# modbrainsv0_4.net
KiCad netlist of a schematic drawn in EAGLE
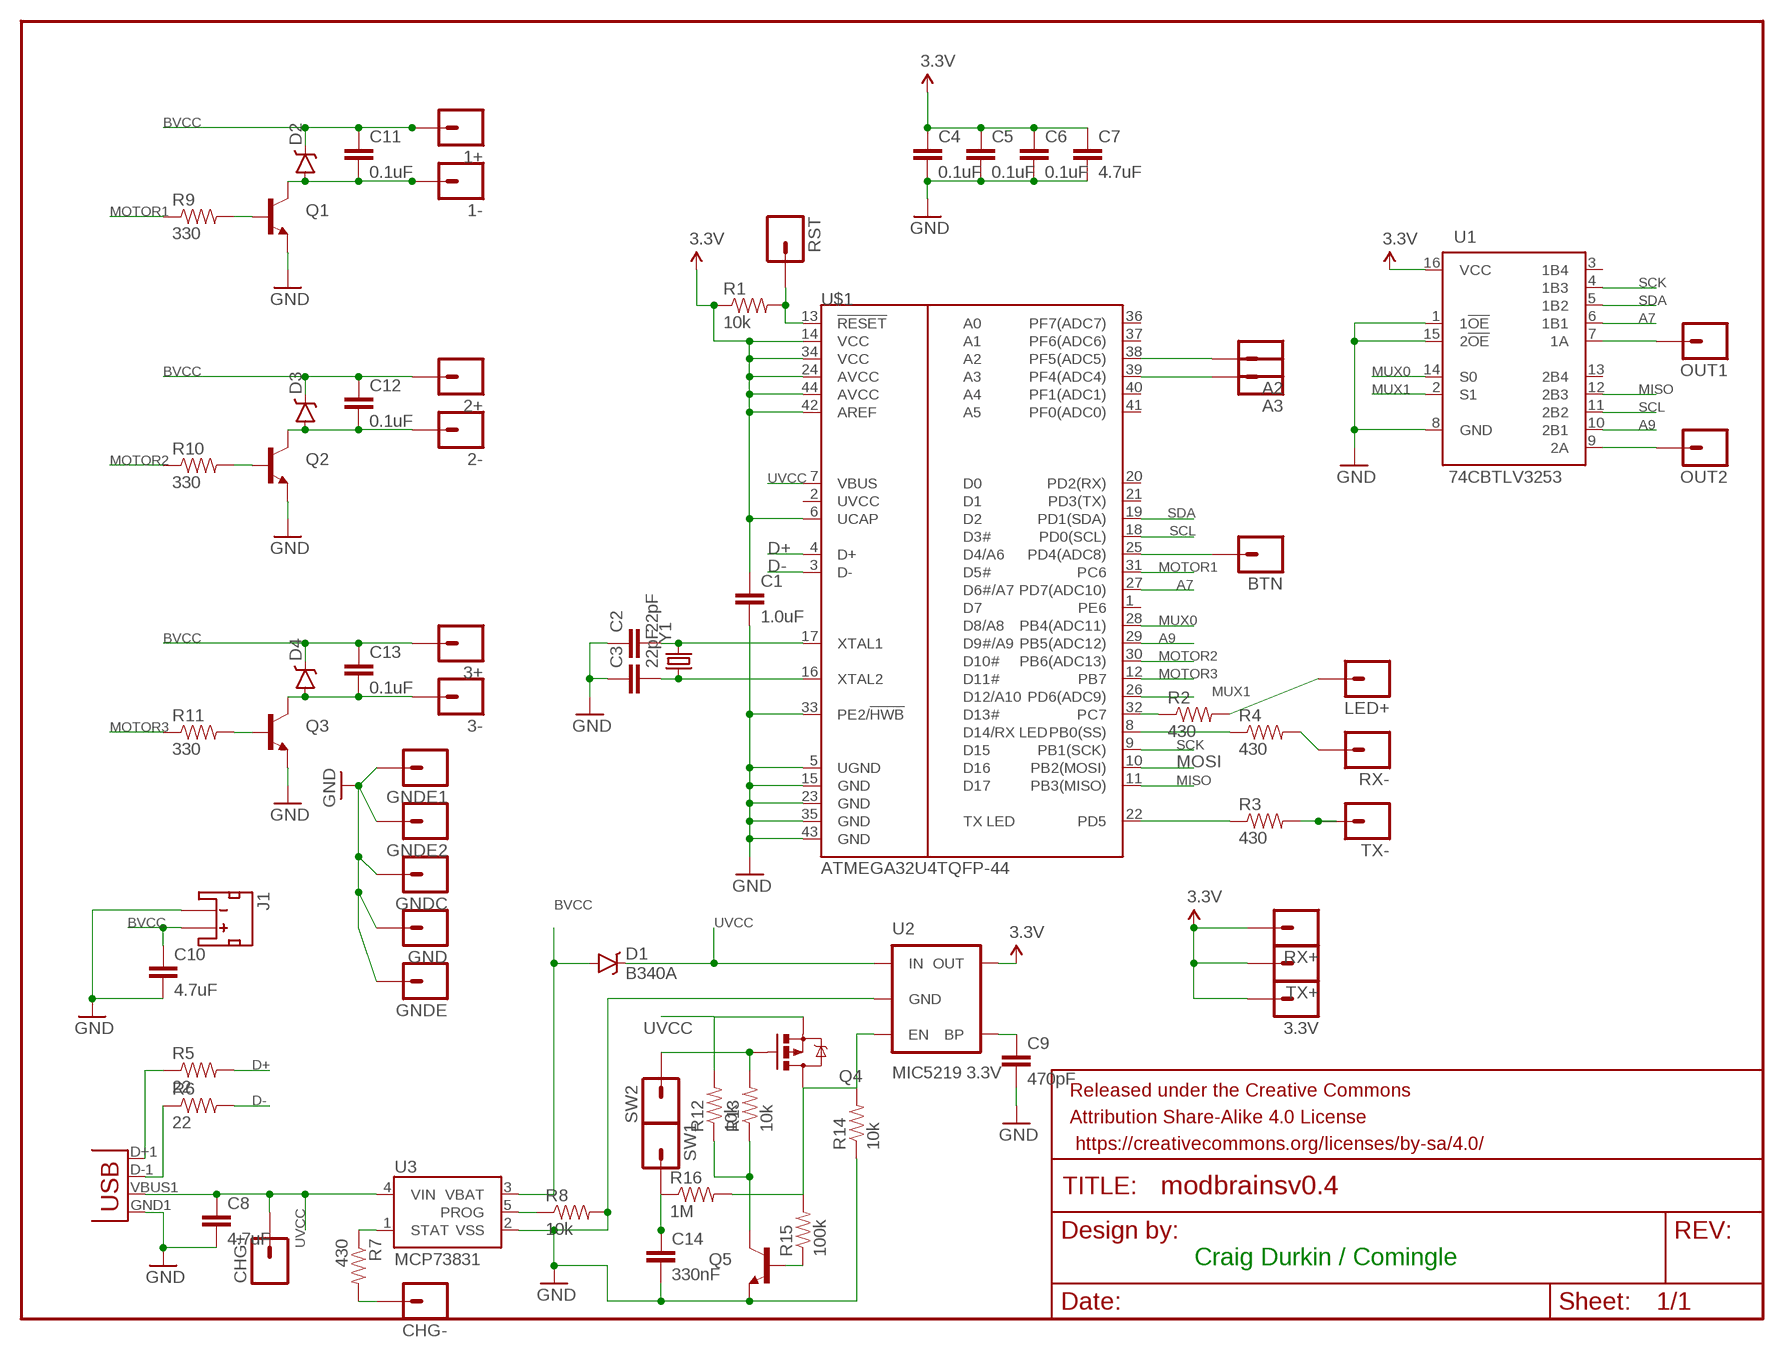
[diagram p0: schematic, sheet 1]

(export (version "E")
  (design (tool "Eeschema 10.0.6"))
  (components
    (comp (ref "1+")
      (value "M01PTH")
      (footprint "eagle-import:1X01")
      (libsource (lib "eagle-import") (part "M01PTH"))
    )
    (comp (ref "1-")
      (value "M01PTH")
      (footprint "eagle-import:1X01")
      (libsource (lib "eagle-import") (part "M01PTH"))
    )
    (comp (ref "2+")
      (value "M01PTH")
      (footprint "eagle-import:1X01")
      (libsource (lib "eagle-import") (part "M01PTH"))
    )
    (comp (ref "2-")
      (value "M01PTH")
      (footprint "eagle-import:1X01")
      (libsource (lib "eagle-import") (part "M01PTH"))
    )
    (comp (ref "3+")
      (value "M01PTH")
      (footprint "eagle-import:1X01")
      (libsource (lib "eagle-import") (part "M01PTH"))
    )
    (comp (ref "3-")
      (value "M01PTH")
      (footprint "eagle-import:1X01")
      (libsource (lib "eagle-import") (part "M01PTH"))
    )
    (comp (ref "3.3V")
      (value "M01PTH")
      (footprint "eagle-import:1X01")
      (libsource (lib "eagle-import") (part "M01PTH"))
    )
    (comp (ref "A2")
      (value "M01PTH")
      (footprint "eagle-import:1X01")
      (libsource (lib "eagle-import") (part "M01PTH"))
    )
    (comp (ref "A3")
      (value "M01PTH")
      (footprint "eagle-import:1X01")
      (libsource (lib "eagle-import") (part "M01PTH"))
    )
    (comp (ref "BTN")
      (value "M01PTH")
      (footprint "eagle-import:1X01")
      (libsource (lib "eagle-import") (part "M01PTH"))
    )
    (comp (ref "C1")
      (value "1.0uF")
      (footprint "eagle-import:0603-CAP")
      (libsource (lib "eagle-import") (part "1.0UF-16V-10%(0603)"))
    )
    (comp (ref "C2")
      (value "22pF")
      (footprint "eagle-import:0603-CAP")
      (libsource (lib "eagle-import") (part "22PF-50V-5%(0603)"))
    )
    (comp (ref "C3")
      (value "22pF")
      (footprint "eagle-import:0603-CAP")
      (libsource (lib "eagle-import") (part "22PF-50V-5%(0603)"))
    )
    (comp (ref "C4")
      (value "0.1uF")
      (footprint "eagle-import:0603-CAP")
      (libsource (lib "eagle-import") (part "SparkFun-Passives_CAP0603-CAP"))
    )
    (comp (ref "C5")
      (value "0.1uF")
      (footprint "eagle-import:0603-CAP")
      (libsource (lib "eagle-import") (part "SparkFun-Passives_CAP0603-CAP"))
    )
    (comp (ref "C6")
      (value "0.1uF")
      (footprint "eagle-import:0603-CAP")
      (libsource (lib "eagle-import") (part "SparkFun-Passives_CAP0603-CAP"))
    )
    (comp (ref "C7")
      (value "4.7uF")
      (footprint "eagle-import:0603-CAP")
      (libsource (lib "eagle-import") (part "SparkFun-Passives_CAP0603-CAP"))
    )
    (comp (ref "C8")
      (value "4.7uF")
      (footprint "eagle-import:1206")
      (libsource (lib "eagle-import") (part "SparkFun-Passives_CAP1206"))
    )
    (comp (ref "C9")
      (value "470pF")
      (footprint "eagle-import:0603-CAP")
      (libsource (lib "eagle-import") (part "0.1UF-25V(+80/-20%)(0603)"))
    )
    (comp (ref "C10")
      (value "4.7uF")
      (footprint "eagle-import:1206")
      (libsource (lib "eagle-import") (part "SparkFun-Passives_CAP1206"))
    )
    (comp (ref "C11")
      (value "0.1uF")
      (footprint "eagle-import:0603-CAP")
      (libsource (lib "eagle-import") (part "0.1UF-25V(+80/-20%)(0603)"))
    )
    (comp (ref "C12")
      (value "0.1uF")
      (footprint "eagle-import:0603-CAP")
      (libsource (lib "eagle-import") (part "0.1UF-25V(+80/-20%)(0603)"))
    )
    (comp (ref "C13")
      (value "0.1uF")
      (footprint "eagle-import:0603-CAP")
      (libsource (lib "eagle-import") (part "0.1UF-25V(+80/-20%)(0603)"))
    )
    (comp (ref "C14")
      (value "330nF")
      (footprint "eagle-import:0603-CAP")
      (libsource (lib "eagle-import") (part "CAP0603-CAP"))
    )
    (comp (ref "CHG+")
      (value "M01PTH")
      (footprint "eagle-import:1X01")
      (libsource (lib "eagle-import") (part "M01PTH"))
    )
    (comp (ref "CHG-")
      (value "M01PTH")
      (footprint "eagle-import:1X01")
      (libsource (lib "eagle-import") (part "M01PTH"))
    )
    (comp (ref "D1")
      (value "B340A")
      (footprint "eagle-import:SMA-DIODE")
      (libsource (lib "eagle-import") (part "DIODE-SCHOTTKY-B340A"))
    )
    (comp (ref "D2")
      (value "BAT20JFILM")
      (footprint "eagle-import:SOD-323")
      (libsource (lib "eagle-import") (part "BAT20JFILM"))
    )
    (comp (ref "D3")
      (value "BAT20JFILM")
      (footprint "eagle-import:SOD-323")
      (libsource (lib "eagle-import") (part "BAT20JFILM"))
    )
    (comp (ref "D4")
      (value "BAT20JFILM")
      (footprint "eagle-import:SOD-323")
      (libsource (lib "eagle-import") (part "BAT20JFILM"))
    )
    (comp (ref "FRAME1")
      (value "FRAME-LETTER")
      (footprint "eagle-import:CREATIVE_COMMONS")
      (libsource (lib "eagle-import") (part "FRAME-LETTER"))
    )
    (comp (ref "GND")
      (value "M01PTH")
      (footprint "eagle-import:1X01")
      (libsource (lib "eagle-import") (part "M01PTH"))
    )
    (comp (ref "GNDC")
      (value "M01PTH")
      (footprint "eagle-import:1X01")
      (libsource (lib "eagle-import") (part "M01PTH"))
    )
    (comp (ref "GNDE")
      (value "M01PTH")
      (footprint "eagle-import:1X01")
      (libsource (lib "eagle-import") (part "M01PTH"))
    )
    (comp (ref "GNDE1")
      (value "M01PTH")
      (footprint "eagle-import:1X01")
      (libsource (lib "eagle-import") (part "M01PTH"))
    )
    (comp (ref "GNDE2")
      (value "M01PTH")
      (footprint "eagle-import:1X01")
      (libsource (lib "eagle-import") (part "M01PTH"))
    )
    (comp (ref "J1")
      (value "JST_2MM_MALE")
      (footprint "eagle-import:JST-2-SMD")
      (libsource (lib "eagle-import") (part "JST_2MM_MALE"))
    )
    (comp (ref "JP4")
      (value "USB")
      (footprint "eagle-import:USB-B-MICRO-SMD_V03")
      (libsource (lib "eagle-import") (part "USB"))
    )
    (comp (ref "LED+")
      (value "M01PTH")
      (footprint "eagle-import:1X01")
      (libsource (lib "eagle-import") (part "M01PTH"))
    )
    (comp (ref "OUT1")
      (value "M01PTH")
      (footprint "eagle-import:1X01")
      (libsource (lib "eagle-import") (part "M01PTH"))
    )
    (comp (ref "OUT2")
      (value "M01PTH")
      (footprint "eagle-import:1X01")
      (libsource (lib "eagle-import") (part "M01PTH"))
    )
    (comp (ref "Q1")
      (value "TRANSISTOR_NPNSOT23-3")
      (footprint "eagle-import:SOT23-3")
      (libsource (lib "eagle-import") (part "TRANSISTOR_NPNSOT23-3"))
    )
    (comp (ref "Q2")
      (value "TRANSISTOR_NPNSOT23-3")
      (footprint "eagle-import:SOT23-3")
      (libsource (lib "eagle-import") (part "TRANSISTOR_NPNSOT23-3"))
    )
    (comp (ref "Q3")
      (value "TRANSISTOR_NPNSOT23-3")
      (footprint "eagle-import:SOT23-3")
      (libsource (lib "eagle-import") (part "TRANSISTOR_NPNSOT23-3"))
    )
    (comp (ref "Q4")
      (value "MOSFET-PCHANNEL")
      (footprint "eagle-import:SOT23-3")
      (libsource (lib "eagle-import") (part "MOSFET-PCHANNEL"))
    )
    (comp (ref "Q5")
      (value "MMBT2222A")
      (footprint "eagle-import:SOT23-3")
      (libsource (lib "eagle-import") (part "TRANSISTOR_NPNMMBT2222A"))
    )
    (comp (ref "R1")
      (value "10k")
      (footprint "eagle-import:0603-RES")
      (libsource (lib "eagle-import") (part "RESISTOR0603-RES"))
    )
    (comp (ref "R2")
      (value "430")
      (footprint "eagle-import:0603-RES")
      (libsource (lib "eagle-import") (part "RESISTOR0603"))
    )
    (comp (ref "R3")
      (value "430")
      (footprint "eagle-import:0603-RES")
      (libsource (lib "eagle-import") (part "RESISTOR0603"))
    )
    (comp (ref "R4")
      (value "430")
      (footprint "eagle-import:0603-RES")
      (libsource (lib "eagle-import") (part "RESISTOR0603"))
    )
    (comp (ref "R5")
      (value "22")
      (footprint "eagle-import:0603-RES")
      (libsource (lib "eagle-import") (part "RESISTOR0603-RES"))
    )
    (comp (ref "R6")
      (value "22")
      (footprint "eagle-import:0603-RES")
      (libsource (lib "eagle-import") (part "RESISTOR0603-RES"))
    )
    (comp (ref "R7")
      (value "430")
      (footprint "eagle-import:0603-RES")
      (libsource (lib "eagle-import") (part "RESISTOR0603-RES"))
    )
    (comp (ref "R8")
      (value "10k")
      (footprint "eagle-import:0603-RES")
      (libsource (lib "eagle-import") (part "RESISTOR0603-RES"))
    )
    (comp (ref "R9")
      (value "330")
      (footprint "eagle-import:0603-RES")
      (libsource (lib "eagle-import") (part "RESISTOR0603-RES"))
    )
    (comp (ref "R10")
      (value "330")
      (footprint "eagle-import:0603-RES")
      (libsource (lib "eagle-import") (part "RESISTOR0603-RES"))
    )
    (comp (ref "R11")
      (value "330")
      (footprint "eagle-import:0603-RES")
      (libsource (lib "eagle-import") (part "RESISTOR0603-RES"))
    )
    (comp (ref "R12")
      (value "10k")
      (footprint "eagle-import:0603-RES")
      (libsource (lib "eagle-import") (part "RESISTOR0603-RES"))
    )
    (comp (ref "R13")
      (value "10k")
      (footprint "eagle-import:0603-RES")
      (libsource (lib "eagle-import") (part "RESISTOR0603-RES"))
    )
    (comp (ref "R14")
      (value "10k")
      (footprint "eagle-import:0603-RES")
      (libsource (lib "eagle-import") (part "RESISTOR0603-RES"))
    )
    (comp (ref "R15")
      (value "100k")
      (footprint "eagle-import:0603-RES")
      (libsource (lib "eagle-import") (part "RESISTOR0603-RES"))
    )
    (comp (ref "R16")
      (value "1M")
      (footprint "eagle-import:0603-RES")
      (libsource (lib "eagle-import") (part "RESISTOR0603-RES"))
    )
    (comp (ref "RST")
      (value "M01PTH")
      (footprint "eagle-import:1X01")
      (libsource (lib "eagle-import") (part "M01PTH"))
    )
    (comp (ref "RX+")
      (value "M01PTH")
      (footprint "eagle-import:1X01")
      (libsource (lib "eagle-import") (part "M01PTH"))
    )
    (comp (ref "RX-")
      (value "M01PTH")
      (footprint "eagle-import:1X01")
      (libsource (lib "eagle-import") (part "M01PTH"))
    )
    (comp (ref "SW1")
      (value "M01PTH")
      (footprint "eagle-import:1X01")
      (libsource (lib "eagle-import") (part "M01PTH"))
    )
    (comp (ref "SW2")
      (value "M01PTH")
      (footprint "eagle-import:1X01")
      (libsource (lib "eagle-import") (part "M01PTH"))
    )
    (comp (ref "TX+")
      (value "M01PTH")
      (footprint "eagle-import:1X01")
      (libsource (lib "eagle-import") (part "M01PTH"))
    )
    (comp (ref "TX-")
      (value "M01PTH")
      (footprint "eagle-import:1X01")
      (libsource (lib "eagle-import") (part "M01PTH"))
    )
    (comp (ref "U$1")
      (value "ATMEGA32U4TQFP-44")
      (footprint "eagle-import:TQFP44")
      (libsource (lib "eagle-import") (part "ATMEGA32U4TQFP-44"))
    )
    (comp (ref "U1")
      (value "74CBTLV3253")
      (footprint "eagle-import:SSOP16-PRACTICE")
      (libsource (lib "eagle-import") (part "74CBTLV3253"))
    )
    (comp (ref "U2")
      (value "MIC5219 3.3V")
      (footprint "eagle-import:SOT23-5")
      (libsource (lib "eagle-import") (part "V_REG_MIC52193.3V"))
    )
    (comp (ref "U3")
      (value "MCP73831")
      (footprint "eagle-import:SOT23-5")
      (libsource (lib "eagle-import") (part "MCP73831"))
    )
    (comp (ref "Y1")
      (value "CRYSTAL5X3")
      (footprint "eagle-import:CRYSTAL-SMD-5X3")
      (libsource (lib "eagle-import") (part "CRYSTAL5X3"))
    )
  )
  (nets
    (net (code "1") (name "/A7") (class "Default")
      (node (ref "U$1") (pin "27") (pinfunction "PD7(ADC10)_27") (pintype "bidirectional"))
      (node (ref "U1") (pin "6") (pinfunction "1B1_6") (pintype "bidirectional"))
    )
    (net (code "2") (name "/A9") (class "Default")
      (node (ref "U$1") (pin "29") (pinfunction "PB5(ADC12)_29") (pintype "bidirectional"))
      (node (ref "U1") (pin "10") (pinfunction "2B1_10") (pintype "bidirectional"))
    )
    (net (code "3") (name "/BVCC") (class "Default")
      (node (ref "1+") (pin "1") (pinfunction "1_1") (pintype "passive"))
      (node (ref "2+") (pin "1") (pinfunction "1_1") (pintype "passive"))
      (node (ref "3+") (pin "1") (pinfunction "1_1") (pintype "passive"))
      (node (ref "C10") (pin "1") (pinfunction "1_1") (pintype "passive"))
      (node (ref "C11") (pin "1") (pinfunction "1_1") (pintype "passive"))
      (node (ref "C12") (pin "1") (pinfunction "1_1") (pintype "passive"))
      (node (ref "C13") (pin "1") (pinfunction "1_1") (pintype "passive"))
      (node (ref "D1") (pin "A") (pinfunction "A_A") (pintype "passive"))
      (node (ref "D2") (pin "C") (pinfunction "C_C") (pintype "passive"))
      (node (ref "D3") (pin "C") (pinfunction "C_C") (pintype "passive"))
      (node (ref "D4") (pin "C") (pinfunction "C_C") (pintype "passive"))
      (node (ref "J1") (pin "2") (pinfunction "+_2") (pintype "bidirectional"))
      (node (ref "U3") (pin "3") (pinfunction "VBAT_3") (pintype "power_in"))
    )
    (net (code "4") (name "/D+") (class "Default")
      (node (ref "R5") (pin "2") (pinfunction "2_2") (pintype "passive"))
      (node (ref "U$1") (pin "4") (pinfunction "D+_4") (pintype "bidirectional"))
    )
    (net (code "5") (name "/D-") (class "Default")
      (node (ref "R6") (pin "2") (pinfunction "2_2") (pintype "passive"))
      (node (ref "U$1") (pin "3") (pinfunction "D-_3") (pintype "bidirectional"))
    )
    (net (code "6") (name "/MISO") (class "Default")
      (node (ref "U$1") (pin "11") (pinfunction "PB3(MISO)_11") (pintype "bidirectional"))
      (node (ref "U1") (pin "12") (pinfunction "2B3_12") (pintype "bidirectional"))
    )
    (net (code "7") (name "/MOSI") (class "Default")
      (node (ref "U$1") (pin "10") (pinfunction "PB2(MOSI)_10") (pintype "bidirectional"))
    )
    (net (code "8") (name "/MOTOR1") (class "Default")
      (node (ref "R9") (pin "1") (pinfunction "1_1") (pintype "passive"))
      (node (ref "U$1") (pin "31") (pinfunction "PC6_31") (pintype "bidirectional"))
    )
    (net (code "9") (name "/MOTOR2") (class "Default")
      (node (ref "R10") (pin "1") (pinfunction "1_1") (pintype "passive"))
      (node (ref "U$1") (pin "30") (pinfunction "PB6(ADC13)_30") (pintype "bidirectional"))
    )
    (net (code "10") (name "/MOTOR3") (class "Default")
      (node (ref "R11") (pin "1") (pinfunction "1_1") (pintype "passive"))
      (node (ref "U$1") (pin "12") (pinfunction "PB7_12") (pintype "bidirectional"))
    )
    (net (code "11") (name "/MUX0") (class "Default")
      (node (ref "U$1") (pin "28") (pinfunction "PB4(ADC11)_28") (pintype "bidirectional"))
      (node (ref "U1") (pin "14") (pinfunction "S0_14") (pintype "bidirectional"))
    )
    (net (code "12") (name "/MUX1") (class "Default")
      (node (ref "U$1") (pin "26") (pinfunction "PD6(ADC9)_26") (pintype "bidirectional"))
      (node (ref "U1") (pin "2") (pinfunction "S1_2") (pintype "bidirectional"))
    )
    (net (code "13") (name "/SCK") (class "Default")
      (node (ref "U$1") (pin "9") (pinfunction "PB1(SCK)_9") (pintype "bidirectional"))
      (node (ref "U1") (pin "4") (pinfunction "1B3_4") (pintype "bidirectional"))
    )
    (net (code "14") (name "/SCL") (class "Default")
      (node (ref "U$1") (pin "18") (pinfunction "PD0(SCL)_18") (pintype "bidirectional"))
      (node (ref "U1") (pin "11") (pinfunction "2B2_11") (pintype "bidirectional"))
    )
    (net (code "15") (name "/SDA") (class "Default")
      (node (ref "U$1") (pin "19") (pinfunction "PD1(SDA)_19") (pintype "bidirectional"))
      (node (ref "U1") (pin "5") (pinfunction "1B2_5") (pintype "bidirectional"))
    )
    (net (code "16") (name "/UVCC") (class "Default")
      (node (ref "C8") (pin "1") (pinfunction "1_1") (pintype "passive"))
      (node (ref "CHG+") (pin "1") (pinfunction "1_1") (pintype "passive"))
      (node (ref "D1") (pin "C") (pinfunction "C_C") (pintype "passive"))
      (node (ref "JP4") (pin "VBUS1") (pinfunction "VBUS_VBUS1") (pintype "bidirectional"))
      (node (ref "Q4") (pin "2") (pinfunction "S_2") (pintype "passive"))
      (node (ref "R12") (pin "2") (pinfunction "2_2") (pintype "passive"))
      (node (ref "U$1") (pin "7") (pinfunction "VBUS_7") (pintype "bidirectional"))
      (node (ref "U2") (pin "1") (pinfunction "IN_1") (pintype "input"))
      (node (ref "U3") (pin "4") (pinfunction "VIN_4") (pintype "power_in"))
    )
    (net (code "17") (name "3.3V") (class "Default")
      (node (ref "3.3V") (pin "1") (pinfunction "1_1") (pintype "passive"))
      (node (ref "C1") (pin "1") (pinfunction "1_1") (pintype "passive"))
      (node (ref "C4") (pin "1") (pinfunction "1_1") (pintype "passive"))
      (node (ref "C5") (pin "1") (pinfunction "1_1") (pintype "passive"))
      (node (ref "C6") (pin "1") (pinfunction "1_1") (pintype "passive"))
      (node (ref "C7") (pin "1") (pinfunction "1_1") (pintype "passive"))
      (node (ref "R1") (pin "1") (pinfunction "1_1") (pintype "passive"))
      (node (ref "RX+") (pin "1") (pinfunction "1_1") (pintype "passive"))
      (node (ref "TX+") (pin "1") (pinfunction "1_1") (pintype "passive"))
      (node (ref "U$1") (pin "14") (pinfunction "VCC_14") (pintype "bidirectional"))
      (node (ref "U$1") (pin "24") (pinfunction "AVCC_24") (pintype "bidirectional"))
      (node (ref "U$1") (pin "34") (pinfunction "VCC_34") (pintype "bidirectional"))
      (node (ref "U$1") (pin "42") (pinfunction "AREF_42") (pintype "bidirectional"))
      (node (ref "U$1") (pin "44") (pinfunction "AVCC_44") (pintype "bidirectional"))
      (node (ref "U$1") (pin "6") (pinfunction "UCAP_6") (pintype "bidirectional"))
      (node (ref "U1") (pin "16") (pinfunction "VCC_16") (pintype "power_in"))
      (node (ref "U2") (pin "5") (pinfunction "OUT_5") (pintype "passive"))
    )
    (net (code "18") (name "GND") (class "Default")
      (node (ref "C1") (pin "2") (pinfunction "2_2") (pintype "passive"))
      (node (ref "C10") (pin "2") (pinfunction "2_2") (pintype "passive"))
      (node (ref "C14") (pin "2") (pinfunction "2_2") (pintype "passive"))
      (node (ref "C2") (pin "1") (pinfunction "1_1") (pintype "passive"))
      (node (ref "C3") (pin "1") (pinfunction "1_1") (pintype "passive"))
      (node (ref "C4") (pin "2") (pinfunction "2_2") (pintype "passive"))
      (node (ref "C5") (pin "2") (pinfunction "2_2") (pintype "passive"))
      (node (ref "C6") (pin "2") (pinfunction "2_2") (pintype "passive"))
      (node (ref "C7") (pin "2") (pinfunction "2_2") (pintype "passive"))
      (node (ref "C8") (pin "2") (pinfunction "2_2") (pintype "passive"))
      (node (ref "C9") (pin "2") (pinfunction "2_2") (pintype "passive"))
      (node (ref "GND") (pin "1") (pinfunction "1_1") (pintype "passive"))
      (node (ref "GNDC") (pin "1") (pinfunction "1_1") (pintype "passive"))
      (node (ref "GNDE") (pin "1") (pinfunction "1_1") (pintype "passive"))
      (node (ref "GNDE1") (pin "1") (pinfunction "1_1") (pintype "passive"))
      (node (ref "GNDE2") (pin "1") (pinfunction "1_1") (pintype "passive"))
      (node (ref "J1") (pin "1") (pinfunction "-_1") (pintype "bidirectional"))
      (node (ref "JP4") (pin "GND1") (pinfunction "GND_GND1") (pintype "bidirectional"))
      (node (ref "Q1") (pin "2") (pinfunction "E_2") (pintype "passive"))
      (node (ref "Q2") (pin "2") (pinfunction "E_2") (pintype "passive"))
      (node (ref "Q3") (pin "2") (pinfunction "E_2") (pintype "passive"))
      (node (ref "Q5") (pin "2") (pinfunction "E_2") (pintype "passive"))
      (node (ref "R14") (pin "1") (pinfunction "1_1") (pintype "passive"))
      (node (ref "R8") (pin "2") (pinfunction "2_2") (pintype "passive"))
      (node (ref "U$1") (pin "15") (pinfunction "GND_15") (pintype "bidirectional"))
      (node (ref "U$1") (pin "23") (pinfunction "GND_23") (pintype "bidirectional"))
      (node (ref "U$1") (pin "33") (pinfunction "PE2/~{HWB}_33") (pintype "bidirectional"))
      (node (ref "U$1") (pin "35") (pinfunction "GND_35") (pintype "bidirectional"))
      (node (ref "U$1") (pin "43") (pinfunction "GND_43") (pintype "bidirectional"))
      (node (ref "U$1") (pin "5") (pinfunction "UGND_5") (pintype "bidirectional"))
      (node (ref "U1") (pin "1") (pinfunction "1~{OE}_1") (pintype "input"))
      (node (ref "U1") (pin "15") (pinfunction "2~{OE}_15") (pintype "input"))
      (node (ref "U1") (pin "8") (pinfunction "GND_8") (pintype "power_in"))
      (node (ref "U2") (pin "2") (pinfunction "GND_2") (pintype "input"))
      (node (ref "U3") (pin "2") (pinfunction "VSS_2") (pintype "power_in"))
    )
    (net (code "19") (name "Net-(C14-Pad1)") (class "Default")
      (node (ref "C14") (pin "1") (pinfunction "1_1") (pintype "passive"))
      (node (ref "R16") (pin "1") (pinfunction "1_1") (pintype "passive"))
      (node (ref "SW1") (pin "1") (pinfunction "1_1") (pintype "passive"))
    )
    (net (code "20") (name "Net-(CHG--Pad1)") (class "Default")
      (node (ref "CHG-") (pin "1") (pinfunction "1_1") (pintype "passive"))
      (node (ref "R7") (pin "2") (pinfunction "2_2") (pintype "passive"))
    )
    (net (code "21") (name "Net-(JP4-D+)") (class "Default")
      (node (ref "JP4") (pin "D+1") (pinfunction "D+_D+1") (pintype "bidirectional"))
      (node (ref "R5") (pin "1") (pinfunction "1_1") (pintype "passive"))
    )
    (net (code "22") (name "Net-(JP4-D-)") (class "Default")
      (node (ref "JP4") (pin "D-1") (pinfunction "D-_D-1") (pintype "bidirectional"))
      (node (ref "R6") (pin "1") (pinfunction "1_1") (pintype "passive"))
    )
    (net (code "23") (name "Net-(LED+-Pad1)") (class "Default")
      (node (ref "LED+") (pin "1") (pinfunction "1_1") (pintype "passive"))
      (node (ref "R2") (pin "2") (pinfunction "2_2") (pintype "passive"))
    )
    (net (code "24") (name "Net-(Q1-B)") (class "Default")
      (node (ref "Q1") (pin "1") (pinfunction "B_1") (pintype "passive"))
      (node (ref "R9") (pin "2") (pinfunction "2_2") (pintype "passive"))
    )
    (net (code "25") (name "Net-(Q1-C)") (class "Default")
      (node (ref "1-") (pin "1") (pinfunction "1_1") (pintype "passive"))
      (node (ref "C11") (pin "2") (pinfunction "2_2") (pintype "passive"))
      (node (ref "D2") (pin "A") (pinfunction "A_A") (pintype "passive"))
      (node (ref "Q1") (pin "3") (pinfunction "C_3") (pintype "passive"))
    )
    (net (code "26") (name "Net-(Q2-B)") (class "Default")
      (node (ref "Q2") (pin "1") (pinfunction "B_1") (pintype "passive"))
      (node (ref "R10") (pin "2") (pinfunction "2_2") (pintype "passive"))
    )
    (net (code "27") (name "Net-(Q2-C)") (class "Default")
      (node (ref "2-") (pin "1") (pinfunction "1_1") (pintype "passive"))
      (node (ref "C12") (pin "2") (pinfunction "2_2") (pintype "passive"))
      (node (ref "D3") (pin "A") (pinfunction "A_A") (pintype "passive"))
      (node (ref "Q2") (pin "3") (pinfunction "C_3") (pintype "passive"))
    )
    (net (code "28") (name "Net-(Q3-B)") (class "Default")
      (node (ref "Q3") (pin "1") (pinfunction "B_1") (pintype "passive"))
      (node (ref "R11") (pin "2") (pinfunction "2_2") (pintype "passive"))
    )
    (net (code "29") (name "Net-(Q3-C)") (class "Default")
      (node (ref "3-") (pin "1") (pinfunction "1_1") (pintype "passive"))
      (node (ref "C13") (pin "2") (pinfunction "2_2") (pintype "passive"))
      (node (ref "D4") (pin "A") (pinfunction "A_A") (pintype "passive"))
      (node (ref "Q3") (pin "3") (pinfunction "C_3") (pintype "passive"))
    )
    (net (code "30") (name "Net-(Q4-D)") (class "Default")
      (node (ref "Q4") (pin "3") (pinfunction "D_3") (pintype "passive"))
      (node (ref "R14") (pin "2") (pinfunction "2_2") (pintype "passive"))
      (node (ref "R15") (pin "2") (pinfunction "2_2") (pintype "passive"))
      (node (ref "R16") (pin "2") (pinfunction "2_2") (pintype "passive"))
      (node (ref "U2") (pin "3") (pinfunction "EN_3") (pintype "input"))
    )
    (net (code "31") (name "Net-(Q4-G)") (class "Default")
      (node (ref "Q4") (pin "1") (pinfunction "G_1") (pintype "passive"))
      (node (ref "R13") (pin "2") (pinfunction "2_2") (pintype "passive"))
      (node (ref "SW2") (pin "1") (pinfunction "1_1") (pintype "passive"))
    )
    (net (code "32") (name "Net-(Q5-B)") (class "Default")
      (node (ref "Q5") (pin "1") (pinfunction "B_1") (pintype "passive"))
      (node (ref "R15") (pin "1") (pinfunction "1_1") (pintype "passive"))
    )
    (net (code "33") (name "Net-(Q5-C)") (class "Default")
      (node (ref "Q5") (pin "3") (pinfunction "C_3") (pintype "passive"))
      (node (ref "R12") (pin "1") (pinfunction "1_1") (pintype "passive"))
      (node (ref "R13") (pin "1") (pinfunction "1_1") (pintype "passive"))
    )
    (net (code "34") (name "Net-(R3-Pad2)") (class "Default")
      (node (ref "R3") (pin "2") (pinfunction "2_2") (pintype "passive"))
      (node (ref "TX-") (pin "1") (pinfunction "1_1") (pintype "passive"))
    )
    (net (code "35") (name "Net-(R4-Pad2)") (class "Default")
      (node (ref "R4") (pin "2") (pinfunction "2_2") (pintype "passive"))
      (node (ref "RX-") (pin "1") (pinfunction "1_1") (pintype "passive"))
    )
    (net (code "36") (name "Net-(U$1-PB0(SS))") (class "Default")
      (node (ref "R4") (pin "1") (pinfunction "1_1") (pintype "passive"))
      (node (ref "U$1") (pin "8") (pinfunction "PB0(SS)_8") (pintype "bidirectional"))
    )
    (net (code "37") (name "Net-(U$1-PC7)") (class "Default")
      (node (ref "R2") (pin "1") (pinfunction "1_1") (pintype "passive"))
      (node (ref "U$1") (pin "32") (pinfunction "PC7_32") (pintype "bidirectional"))
    )
    (net (code "38") (name "Net-(U$1-PD4(ADC8))") (class "Default")
      (node (ref "BTN") (pin "1") (pinfunction "1_1") (pintype "passive"))
      (node (ref "U$1") (pin "25") (pinfunction "PD4(ADC8)_25") (pintype "bidirectional"))
    )
    (net (code "39") (name "Net-(U$1-PD5)") (class "Default")
      (node (ref "R3") (pin "1") (pinfunction "1_1") (pintype "passive"))
      (node (ref "U$1") (pin "22") (pinfunction "PD5_22") (pintype "bidirectional"))
    )
    (net (code "40") (name "Net-(U$1-PF4(ADC4))") (class "Default")
      (node (ref "A3") (pin "1") (pinfunction "1_1") (pintype "passive"))
      (node (ref "U$1") (pin "39") (pinfunction "PF4(ADC4)_39") (pintype "bidirectional"))
    )
    (net (code "41") (name "Net-(U$1-PF5(ADC5))") (class "Default")
      (node (ref "A2") (pin "1") (pinfunction "1_1") (pintype "passive"))
      (node (ref "U$1") (pin "38") (pinfunction "PF5(ADC5)_38") (pintype "bidirectional"))
    )
    (net (code "42") (name "Net-(U$1-XTAL1)") (class "Default")
      (node (ref "C2") (pin "2") (pinfunction "2_2") (pintype "passive"))
      (node (ref "U$1") (pin "17") (pinfunction "XTAL1_17") (pintype "bidirectional"))
      (node (ref "Y1") (pin "3") (pinfunction "2_3") (pintype "passive"))
    )
    (net (code "43") (name "Net-(U$1-XTAL2)") (class "Default")
      (node (ref "C3") (pin "2") (pinfunction "2_2") (pintype "passive"))
      (node (ref "U$1") (pin "16") (pinfunction "XTAL2_16") (pintype "bidirectional"))
      (node (ref "Y1") (pin "1") (pinfunction "1_1") (pintype "passive"))
    )
    (net (code "44") (name "Net-(U$1-~{RESET})") (class "Default")
      (node (ref "R1") (pin "2") (pinfunction "2_2") (pintype "passive"))
      (node (ref "RST") (pin "1") (pinfunction "1_1") (pintype "passive"))
      (node (ref "U$1") (pin "13") (pinfunction "~{RESET}_13") (pintype "bidirectional"))
    )
    (net (code "45") (name "Net-(U1-1A)") (class "Default")
      (node (ref "OUT1") (pin "1") (pinfunction "1_1") (pintype "passive"))
      (node (ref "U1") (pin "7") (pinfunction "1A_7") (pintype "bidirectional"))
    )
    (net (code "46") (name "Net-(U1-2A)") (class "Default")
      (node (ref "OUT2") (pin "1") (pinfunction "1_1") (pintype "passive"))
      (node (ref "U1") (pin "9") (pinfunction "2A_9") (pintype "bidirectional"))
    )
    (net (code "47") (name "Net-(U2-BP)") (class "Default")
      (node (ref "C9") (pin "1") (pinfunction "1_1") (pintype "passive"))
      (node (ref "U2") (pin "4") (pinfunction "BP_4") (pintype "input"))
    )
    (net (code "48") (name "Net-(U3-PROG)") (class "Default")
      (node (ref "R8") (pin "1") (pinfunction "1_1") (pintype "passive"))
      (node (ref "U3") (pin "5") (pinfunction "PROG_5") (pintype "bidirectional"))
    )
    (net (code "49") (name "Net-(U3-STAT)") (class "Default")
      (node (ref "R7") (pin "1") (pinfunction "1_1") (pintype "passive"))
      (node (ref "U3") (pin "1") (pinfunction "STAT_1") (pintype "output"))
    )
    (net (code "50") (name "unconnected-(J1-PAD1-PadNC1)") (class "Default")
      (node (ref "J1") (pin "NC1") (pinfunction "PAD1_NC1") (pintype "bidirectional"))
    )
    (net (code "51") (name "unconnected-(J1-PAD2-PadNC2)") (class "Default")
      (node (ref "J1") (pin "NC2") (pinfunction "PAD2_NC2") (pintype "bidirectional"))
    )
    (net (code "52") (name "unconnected-(U$1-PD2(RX)-Pad20)") (class "Default")
      (node (ref "U$1") (pin "20") (pinfunction "PD2(RX)_20") (pintype "bidirectional"))
    )
    (net (code "53") (name "unconnected-(U$1-PD3(TX)-Pad21)") (class "Default")
      (node (ref "U$1") (pin "21") (pinfunction "PD3(TX)_21") (pintype "bidirectional"))
    )
    (net (code "54") (name "unconnected-(U$1-PE6-Pad1)") (class "Default")
      (node (ref "U$1") (pin "1") (pinfunction "PE6_1") (pintype "bidirectional"))
    )
    (net (code "55") (name "unconnected-(U$1-PF0(ADC0)-Pad41)") (class "Default")
      (node (ref "U$1") (pin "41") (pinfunction "PF0(ADC0)_41") (pintype "bidirectional"))
    )
    (net (code "56") (name "unconnected-(U$1-PF1(ADC1)-Pad40)") (class "Default")
      (node (ref "U$1") (pin "40") (pinfunction "PF1(ADC1)_40") (pintype "bidirectional"))
    )
    (net (code "57") (name "unconnected-(U$1-PF6(ADC6)-Pad37)") (class "Default")
      (node (ref "U$1") (pin "37") (pinfunction "PF6(ADC6)_37") (pintype "bidirectional"))
    )
    (net (code "58") (name "unconnected-(U$1-PF7(ADC7)-Pad36)") (class "Default")
      (node (ref "U$1") (pin "36") (pinfunction "PF7(ADC7)_36") (pintype "bidirectional"))
    )
    (net (code "59") (name "unconnected-(U$1-UVCC-Pad2)") (class "Default")
      (node (ref "U$1") (pin "2") (pinfunction "UVCC_2") (pintype "bidirectional"))
    )
    (net (code "60") (name "unconnected-(U1-1B4-Pad3)") (class "Default")
      (node (ref "U1") (pin "3") (pinfunction "1B4_3") (pintype "bidirectional"))
    )
    (net (code "61") (name "unconnected-(U1-2B4-Pad13)") (class "Default")
      (node (ref "U1") (pin "13") (pinfunction "2B4_13") (pintype "bidirectional"))
    )
  )
)
